# CONTROL.net
KiCad netlist of a schematic drawn in Altium Designer
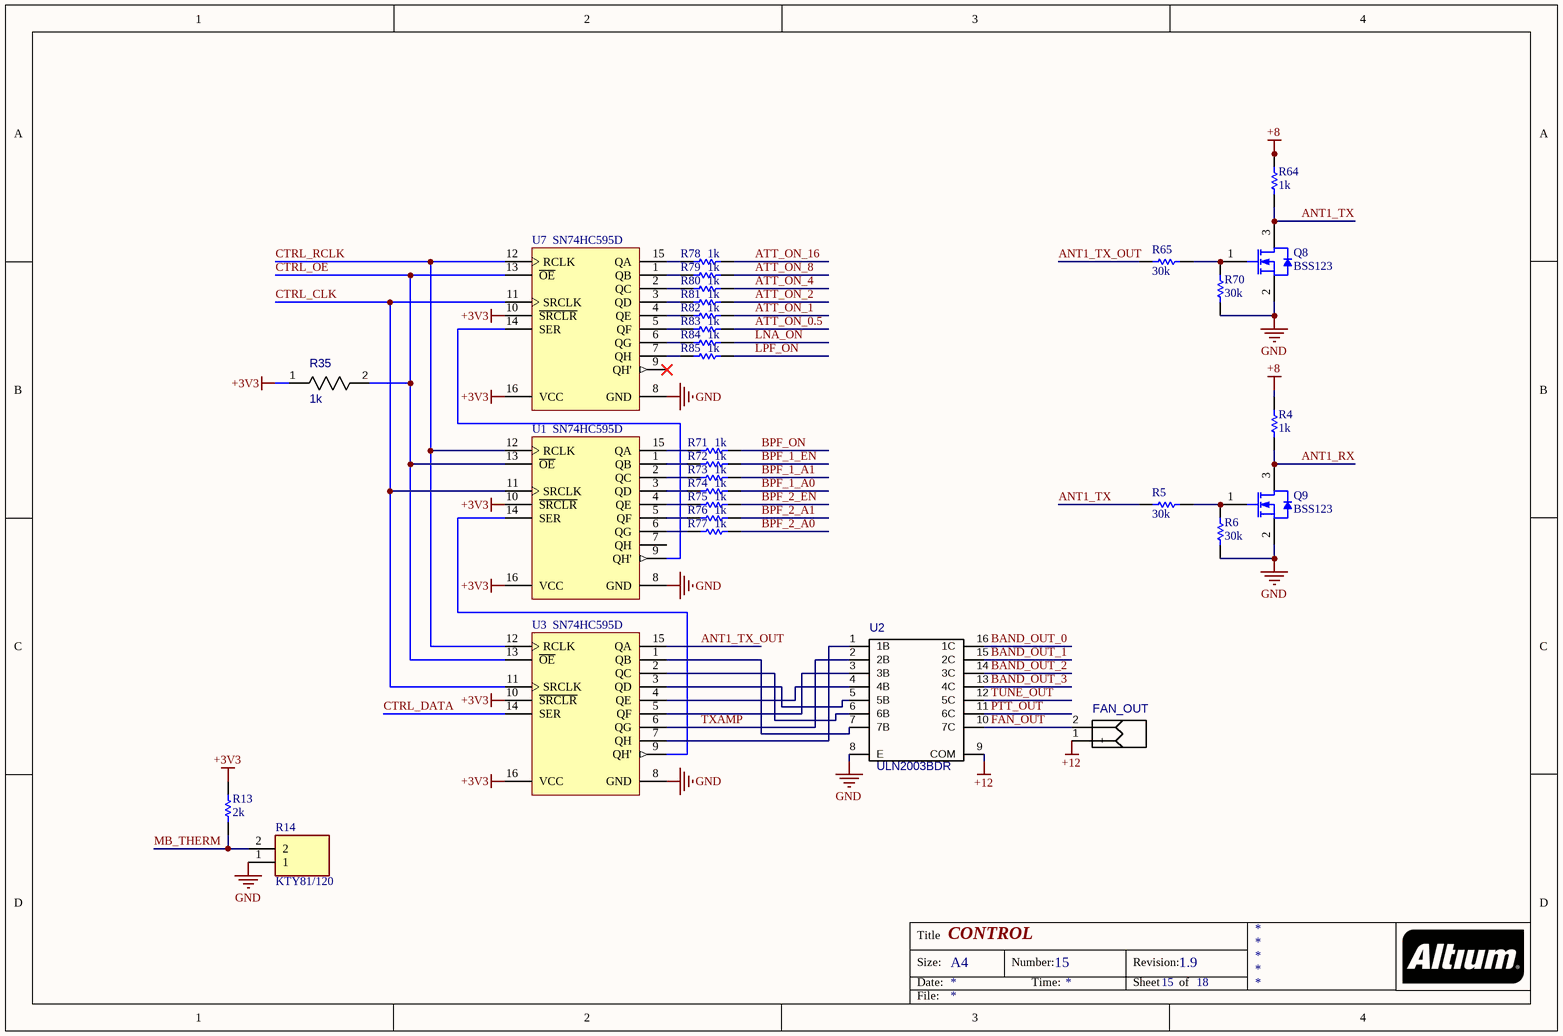
[diagram p0: CONTROL.SchDoc]

(export (version "E")
  (design (tool "Eeschema 10.0.6"))
  (components
    (comp (ref "FAN_OUT")
      (value "51022-0200")
      (footprint "51022-0200")
      (libsource (lib "*") (part "51022-0200"))
    )
    (comp (ref "Q8")
      (value "BSS123")
      (footprint "FAIR-SOT23-3_V")
      (fields (field (name "MANUFACTURER") "Fairchild"))
      (libsource (lib "Altium Content Vault") (part "NEMOS-GSD-3"))
    )
    (comp (ref "Q9")
      (value "BSS123")
      (footprint "FAIR-SOT23-3_V")
      (fields (field (name "MANUFACTURER") "Fairchild"))
      (libsource (lib "Altium Content Vault") (part "NEMOS-GSD-3"))
    )
    (comp (ref "R4")
      (value "1k")
      (footprint "RESC2013X60X40NL20T25")
      (description "RES_0805")
      (fields (field (name "MANUFACTURER") "Panasonic") (field (name "PART NUMBER") "ERA-6AEB303V"))
      (libsource (lib "Altium Content Vault") (part "RES"))
    )
    (comp (ref "R5")
      (value "30k")
      (footprint "RESC2013X60X40NL20T25")
      (description "RES_0805")
      (fields (field (name "MANUFACTURER") "Panasonic") (field (name "PART NUMBER") "ERA-6AEB303V"))
      (libsource (lib "Altium Content Vault") (part "RES"))
    )
    (comp (ref "R6")
      (value "30k")
      (footprint "RESC2013X60X40NL20T25")
      (description "RES_0805")
      (fields (field (name "MANUFACTURER") "Panasonic") (field (name "PART NUMBER") "ERA-6AEB303V"))
      (libsource (lib "Altium Content Vault") (part "RES"))
    )
    (comp (ref "R13")
      (value "2k")
      (footprint "RESC2013X60X40NL20T25")
      (description "RES_0805")
      (fields (field (name "MANUFACTURER") "Panasonic") (field (name "PART NUMBER") "ERA-6AEB303V"))
      (libsource (lib "Altium Content Vault") (part "RES"))
    )
    (comp (ref "R14")
      (value "KTY81/120")
      (footprint "SamacSys:TO254P420X460X770-2P")
      (description "Integrated Circuit")
      (fields (field (name "MANUFACTURER_PART_NUMBER") "KTY81/110"))
      (libsource (lib "*") (part "KTY81_110"))
    )
    (comp (ref "R35")
      (value "1k")
      (footprint "RES_0805")
      (description "RES_0805")
      (libsource (lib "*") (part "RES_0805"))
    )
    (comp (ref "R64")
      (value "1k")
      (footprint "RESC2013X60X40NL20T25")
      (description "RES_0805")
      (fields (field (name "MANUFACTURER") "Panasonic") (field (name "PART NUMBER") "ERA-6AEB303V"))
      (libsource (lib "Altium Content Vault") (part "RES"))
    )
    (comp (ref "R65")
      (value "30k")
      (footprint "RESC2013X60X40NL20T25")
      (description "RES_0805")
      (fields (field (name "MANUFACTURER") "Panasonic") (field (name "PART NUMBER") "ERA-6AEB303V"))
      (libsource (lib "Altium Content Vault") (part "RES"))
    )
    (comp (ref "R70")
      (value "30k")
      (footprint "RESC2013X60X40NL20T25")
      (description "RES_0805")
      (fields (field (name "MANUFACTURER") "Panasonic") (field (name "PART NUMBER") "ERA-6AEB303V"))
      (libsource (lib "Altium Content Vault") (part "RES"))
    )
    (comp (ref "R71")
      (value "1k")
      (footprint "RESC2013X60X40NL20T25")
      (description "RES_0805")
      (fields (field (name "MANUFACTURER") "Panasonic") (field (name "PART NUMBER") "ERA-6AEB303V"))
      (libsource (lib "Altium Content Vault") (part "RES"))
    )
    (comp (ref "R72")
      (value "1k")
      (footprint "RESC2013X60X40NL20T25")
      (description "RES_0805")
      (fields (field (name "MANUFACTURER") "Panasonic") (field (name "PART NUMBER") "ERA-6AEB303V"))
      (libsource (lib "Altium Content Vault") (part "RES"))
    )
    (comp (ref "R73")
      (value "1k")
      (footprint "RESC2013X60X40NL20T25")
      (description "RES_0805")
      (fields (field (name "MANUFACTURER") "Panasonic") (field (name "PART NUMBER") "ERA-6AEB303V"))
      (libsource (lib "Altium Content Vault") (part "RES"))
    )
    (comp (ref "R74")
      (value "1k")
      (footprint "RESC2013X60X40NL20T25")
      (description "RES_0805")
      (fields (field (name "MANUFACTURER") "Panasonic") (field (name "PART NUMBER") "ERA-6AEB303V"))
      (libsource (lib "Altium Content Vault") (part "RES"))
    )
    (comp (ref "R75")
      (value "1k")
      (footprint "RESC2013X60X40NL20T25")
      (description "RES_0805")
      (fields (field (name "MANUFACTURER") "Panasonic") (field (name "PART NUMBER") "ERA-6AEB303V"))
      (libsource (lib "Altium Content Vault") (part "RES"))
    )
    (comp (ref "R76")
      (value "1k")
      (footprint "RESC2013X60X40NL20T25")
      (description "RES_0805")
      (fields (field (name "MANUFACTURER") "Panasonic") (field (name "PART NUMBER") "ERA-6AEB303V"))
      (libsource (lib "Altium Content Vault") (part "RES"))
    )
    (comp (ref "R77")
      (value "1k")
      (footprint "RESC2013X60X40NL20T25")
      (description "RES_0805")
      (fields (field (name "MANUFACTURER") "Panasonic") (field (name "PART NUMBER") "ERA-6AEB303V"))
      (libsource (lib "Altium Content Vault") (part "RES"))
    )
    (comp (ref "R78")
      (value "1k")
      (footprint "RESC2013X60X40NL20T25")
      (description "RES_0805")
      (fields (field (name "MANUFACTURER") "Panasonic") (field (name "PART NUMBER") "ERA-6AEB303V"))
      (libsource (lib "Altium Content Vault") (part "RES"))
    )
    (comp (ref "R79")
      (value "1k")
      (footprint "RESC2013X60X40NL20T25")
      (description "RES_0805")
      (fields (field (name "MANUFACTURER") "Panasonic") (field (name "PART NUMBER") "ERA-6AEB303V"))
      (libsource (lib "Altium Content Vault") (part "RES"))
    )
    (comp (ref "R80")
      (value "1k")
      (footprint "RESC2013X60X40NL20T25")
      (description "RES_0805")
      (fields (field (name "MANUFACTURER") "Panasonic") (field (name "PART NUMBER") "ERA-6AEB303V"))
      (libsource (lib "Altium Content Vault") (part "RES"))
    )
    (comp (ref "R81")
      (value "1k")
      (footprint "RESC2013X60X40NL20T25")
      (description "RES_0805")
      (fields (field (name "MANUFACTURER") "Panasonic") (field (name "PART NUMBER") "ERA-6AEB303V"))
      (libsource (lib "Altium Content Vault") (part "RES"))
    )
    (comp (ref "R82")
      (value "1k")
      (footprint "RESC2013X60X40NL20T25")
      (description "RES_0805")
      (fields (field (name "MANUFACTURER") "Panasonic") (field (name "PART NUMBER") "ERA-6AEB303V"))
      (libsource (lib "Altium Content Vault") (part "RES"))
    )
    (comp (ref "R83")
      (value "1k")
      (footprint "RESC2013X60X40NL20T25")
      (description "RES_0805")
      (fields (field (name "MANUFACTURER") "Panasonic") (field (name "PART NUMBER") "ERA-6AEB303V"))
      (libsource (lib "Altium Content Vault") (part "RES"))
    )
    (comp (ref "R84")
      (value "1k")
      (footprint "RESC2013X60X40NL20T25")
      (description "RES_0805")
      (fields (field (name "MANUFACTURER") "Panasonic") (field (name "PART NUMBER") "ERA-6AEB303V"))
      (libsource (lib "Altium Content Vault") (part "RES"))
    )
    (comp (ref "R85")
      (value "1k")
      (footprint "RESC2013X60X40NL20T25")
      (description "RES_0805")
      (fields (field (name "MANUFACTURER") "Panasonic") (field (name "PART NUMBER") "ERA-6AEB303V"))
      (libsource (lib "Altium Content Vault") (part "RES"))
    )
    (comp (ref "U1")
      (value "SN74HC595D")
      (footprint "D0016A_L")
      (description "8-Bit Shift Registers With 3-State Output Registers, D0016A, TUBE")
      (fields
        (field (name "GENERIC PART NUMBER") "SN74HC595")
        (field (name "MANUFACTURER") "Texas Instruments")
      )
      (libsource (lib "Altium Content Vault") (part "TI-SN74XHCT595X_SN74LV595A-16"))
    )
    (comp (ref "U2")
      (value "ULN2003BDR")
      (footprint "ULN2003BDR")
      (libsource (lib "RF-UNIT") (part "ULN2003BDR"))
    )
    (comp (ref "U3")
      (value "SN74HC595D")
      (footprint "D0016A_L")
      (description "8-Bit Shift Registers With 3-State Output Registers, D0016A, TUBE")
      (fields
        (field (name "GENERIC PART NUMBER") "SN74HC595")
        (field (name "MANUFACTURER") "Texas Instruments")
      )
      (libsource (lib "Altium Content Vault") (part "TI-SN74XHCT595X_SN74LV595A-16"))
    )
    (comp (ref "U7")
      (value "SN74HC595D")
      (footprint "D0016A_L")
      (description "8-Bit Shift Registers With 3-State Output Registers, D0016A, TUBE")
      (fields
        (field (name "GENERIC PART NUMBER") "SN74HC595")
        (field (name "MANUFACTURER") "Texas Instruments")
      )
      (libsource (lib "Altium Content Vault") (part "TI-SN74XHCT595X_SN74LV595A-16"))
    )
  )
  (nets
    (net (code "1") (name "+3V3") (class "Default")
      (node (ref "R13") (pin "1") (pinfunction "1_1") (pintype "passive"))
      (node (ref "R35") (pin "1") (pinfunction "1_1") (pintype "passive"))
      (node (ref "U1") (pin "10") (pinfunction "~{SRCLR}_10") (pintype "passive"))
      (node (ref "U1") (pin "16") (pinfunction "VCC_16") (pintype "power_in"))
      (node (ref "U3") (pin "10") (pinfunction "~{SRCLR}_10") (pintype "passive"))
      (node (ref "U3") (pin "16") (pinfunction "VCC_16") (pintype "power_in"))
      (node (ref "U7") (pin "10") (pinfunction "~{SRCLR}_10") (pintype "passive"))
      (node (ref "U7") (pin "16") (pinfunction "VCC_16") (pintype "power_in"))
    )
    (net (code "2") (name "+8") (class "Default")
      (node (ref "R4") (pin "1") (pinfunction "1_1") (pintype "passive"))
      (node (ref "R64") (pin "1") (pinfunction "1_1") (pintype "passive"))
    )
    (net (code "3") (name "+12") (class "Default")
      (node (ref "FAN_OUT") (pin "1") (pinfunction "+_1") (pintype "passive"))
      (node (ref "U2") (pin "9") (pinfunction "COM_9") (pintype "passive"))
    )
    (net (code "5") (name "/ANT1_RX") (class "Default")
      (node (ref "Q9") (pin "3") (pinfunction "D_3") (pintype "passive"))
      (node (ref "R4") (pin "2") (pinfunction "2_2") (pintype "passive"))
    )
    (net (code "6") (name "/ANT1_TX") (class "Default")
      (node (ref "Q8") (pin "3") (pinfunction "D_3") (pintype "passive"))
      (node (ref "R5") (pin "2") (pinfunction "2_2") (pintype "passive"))
      (node (ref "R64") (pin "2") (pinfunction "2_2") (pintype "passive"))
    )
    (net (code "7") (name "/ANT1_TX_OUT") (class "Default")
      (node (ref "R65") (pin "2") (pinfunction "2_2") (pintype "passive"))
      (node (ref "U3") (pin "15") (pinfunction "QA_15") (pintype "tri_state"))
    )
    (net (code "8") (name "/ATT_ON_0.5") (class "Default")
      (node (ref "R83") (pin "1") (pinfunction "1_1") (pintype "passive"))
    )
    (net (code "9") (name "/ATT_ON_1") (class "Default")
      (node (ref "R82") (pin "1") (pinfunction "1_1") (pintype "passive"))
    )
    (net (code "10") (name "/ATT_ON_2") (class "Default")
      (node (ref "R81") (pin "1") (pinfunction "1_1") (pintype "passive"))
    )
    (net (code "11") (name "/ATT_ON_4") (class "Default")
      (node (ref "R80") (pin "1") (pinfunction "1_1") (pintype "passive"))
    )
    (net (code "12") (name "/ATT_ON_8") (class "Default")
      (node (ref "R79") (pin "1") (pinfunction "1_1") (pintype "passive"))
    )
    (net (code "13") (name "/ATT_ON_16") (class "Default")
      (node (ref "R78") (pin "1") (pinfunction "1_1") (pintype "passive"))
    )
    (net (code "14") (name "/BAND_OUT_0") (class "Default")
      (node (ref "U2") (pin "16") (pinfunction "1C_16") (pintype "passive"))
    )
    (net (code "15") (name "/BAND_OUT_1") (class "Default")
      (node (ref "U2") (pin "15") (pinfunction "2C_15") (pintype "passive"))
    )
    (net (code "16") (name "/BAND_OUT_2") (class "Default")
      (node (ref "U2") (pin "14") (pinfunction "3C_14") (pintype "passive"))
    )
    (net (code "17") (name "/BAND_OUT_3") (class "Default")
      (node (ref "U2") (pin "13") (pinfunction "4C_13") (pintype "passive"))
    )
    (net (code "18") (name "/BPF_1_A0") (class "Default")
      (node (ref "R74") (pin "1") (pinfunction "1_1") (pintype "passive"))
    )
    (net (code "19") (name "/BPF_1_A1") (class "Default")
      (node (ref "R73") (pin "1") (pinfunction "1_1") (pintype "passive"))
    )
    (net (code "20") (name "/BPF_1_EN") (class "Default")
      (node (ref "R72") (pin "1") (pinfunction "1_1") (pintype "passive"))
    )
    (net (code "21") (name "/BPF_2_A0") (class "Default")
      (node (ref "R77") (pin "1") (pinfunction "1_1") (pintype "passive"))
    )
    (net (code "22") (name "/BPF_2_A1") (class "Default")
      (node (ref "R76") (pin "1") (pinfunction "1_1") (pintype "passive"))
    )
    (net (code "23") (name "/BPF_2_EN") (class "Default")
      (node (ref "R75") (pin "1") (pinfunction "1_1") (pintype "passive"))
    )
    (net (code "24") (name "/BPF_ON") (class "Default")
      (node (ref "R71") (pin "1") (pinfunction "1_1") (pintype "passive"))
    )
    (net (code "25") (name "/CTRL_CLK") (class "Default")
      (node (ref "U1") (pin "11") (pinfunction "SRCLK_11") (pintype "passive"))
      (node (ref "U3") (pin "11") (pinfunction "SRCLK_11") (pintype "passive"))
      (node (ref "U7") (pin "11") (pinfunction "SRCLK_11") (pintype "passive"))
    )
    (net (code "26") (name "/CTRL_DATA") (class "Default")
      (node (ref "U3") (pin "14") (pinfunction "SER_14") (pintype "passive"))
    )
    (net (code "27") (name "/CTRL_OE") (class "Default")
      (node (ref "R35") (pin "2") (pinfunction "2_2") (pintype "passive"))
      (node (ref "U1") (pin "13") (pinfunction "~{OE}_13") (pintype "passive"))
      (node (ref "U3") (pin "13") (pinfunction "~{OE}_13") (pintype "passive"))
      (node (ref "U7") (pin "13") (pinfunction "~{OE}_13") (pintype "passive"))
    )
    (net (code "28") (name "/CTRL_RCLK") (class "Default")
      (node (ref "U1") (pin "12") (pinfunction "RCLK_12") (pintype "passive"))
      (node (ref "U3") (pin "12") (pinfunction "RCLK_12") (pintype "passive"))
      (node (ref "U7") (pin "12") (pinfunction "RCLK_12") (pintype "passive"))
    )
    (net (code "29") (name "/FAN_OUT") (class "Default")
      (node (ref "FAN_OUT") (pin "2") (pinfunction "-_2") (pintype "passive"))
      (node (ref "U2") (pin "10") (pinfunction "7C_10") (pintype "passive"))
    )
    (net (code "30") (name "/LNA_ON") (class "Default")
      (node (ref "R84") (pin "1") (pinfunction "1_1") (pintype "passive"))
    )
    (net (code "31") (name "/LPF_ON") (class "Default")
      (node (ref "R85") (pin "1") (pinfunction "1_1") (pintype "passive"))
    )
    (net (code "32") (name "/MB_THERM") (class "Default")
      (node (ref "R13") (pin "2") (pinfunction "2_2") (pintype "passive"))
      (node (ref "R14") (pin "2") (pinfunction "2_2") (pintype "passive"))
    )
    (net (code "33") (name "/PTT_OUT") (class "Default")
      (node (ref "U2") (pin "11") (pinfunction "6C_11") (pintype "passive"))
    )
    (net (code "34") (name "/TUNE_OUT") (class "Default")
      (node (ref "U2") (pin "12") (pinfunction "5C_12") (pintype "passive"))
    )
    (net (code "35") (name "/TXAMP") (class "Default")
      (node (ref "U2") (pin "2") (pinfunction "2B_2") (pintype "passive"))
      (node (ref "U3") (pin "6") (pinfunction "QG_6") (pintype "tri_state"))
    )
    (net (code "36") (name "GND") (class "Default")
      (node (ref "Q8") (pin "2") (pinfunction "S_2") (pintype "passive"))
      (node (ref "Q9") (pin "2") (pinfunction "S_2") (pintype "passive"))
      (node (ref "R14") (pin "1") (pinfunction "1_1") (pintype "passive"))
      (node (ref "R6") (pin "1") (pinfunction "1_1") (pintype "passive"))
      (node (ref "R70") (pin "1") (pinfunction "1_1") (pintype "passive"))
      (node (ref "U1") (pin "8") (pinfunction "GND_8") (pintype "power_in"))
      (node (ref "U2") (pin "8") (pinfunction "E_8") (pintype "passive"))
      (node (ref "U3") (pin "8") (pinfunction "GND_8") (pintype "power_in"))
      (node (ref "U7") (pin "8") (pinfunction "GND_8") (pintype "power_in"))
    )
    (net (code "37") (name "Net-(Q8-G)") (class "Default")
      (node (ref "Q8") (pin "1") (pinfunction "G_1") (pintype "passive"))
      (node (ref "R65") (pin "1") (pinfunction "1_1") (pintype "passive"))
      (node (ref "R70") (pin "2") (pinfunction "2_2") (pintype "passive"))
    )
    (net (code "38") (name "Net-(Q9-G)") (class "Default")
      (node (ref "Q9") (pin "1") (pinfunction "G_1") (pintype "passive"))
      (node (ref "R5") (pin "1") (pinfunction "1_1") (pintype "passive"))
      (node (ref "R6") (pin "2") (pinfunction "2_2") (pintype "passive"))
    )
    (net (code "39") (name "Net-(U1-QA)") (class "Default")
      (node (ref "R71") (pin "2") (pinfunction "2_2") (pintype "passive"))
      (node (ref "U1") (pin "15") (pinfunction "QA_15") (pintype "tri_state"))
    )
    (net (code "40") (name "Net-(U1-QB)") (class "Default")
      (node (ref "R72") (pin "2") (pinfunction "2_2") (pintype "passive"))
      (node (ref "U1") (pin "1") (pinfunction "QB_1") (pintype "tri_state"))
    )
    (net (code "41") (name "Net-(U1-QC)") (class "Default")
      (node (ref "R73") (pin "2") (pinfunction "2_2") (pintype "passive"))
      (node (ref "U1") (pin "2") (pinfunction "QC_2") (pintype "tri_state"))
    )
    (net (code "42") (name "Net-(U1-QD)") (class "Default")
      (node (ref "R74") (pin "2") (pinfunction "2_2") (pintype "passive"))
      (node (ref "U1") (pin "3") (pinfunction "QD_3") (pintype "tri_state"))
    )
    (net (code "43") (name "Net-(U1-QE)") (class "Default")
      (node (ref "R75") (pin "2") (pinfunction "2_2") (pintype "passive"))
      (node (ref "U1") (pin "4") (pinfunction "QE_4") (pintype "tri_state"))
    )
    (net (code "44") (name "Net-(U1-QF)") (class "Default")
      (node (ref "R76") (pin "2") (pinfunction "2_2") (pintype "passive"))
      (node (ref "U1") (pin "5") (pinfunction "QF_5") (pintype "tri_state"))
    )
    (net (code "45") (name "Net-(U1-QG)") (class "Default")
      (node (ref "R77") (pin "2") (pinfunction "2_2") (pintype "passive"))
      (node (ref "U1") (pin "6") (pinfunction "QG_6") (pintype "tri_state"))
    )
    (net (code "46") (name "Net-(U1-QH')") (class "Default")
      (node (ref "U1") (pin "9") (pinfunction "QH'_9") (pintype "output"))
      (node (ref "U7") (pin "14") (pinfunction "SER_14") (pintype "passive"))
    )
    (net (code "47") (name "Net-(U1-SER)") (class "Default")
      (node (ref "U1") (pin "14") (pinfunction "SER_14") (pintype "passive"))
      (node (ref "U3") (pin "9") (pinfunction "QH'_9") (pintype "output"))
    )
    (net (code "48") (name "Net-(U2-1B)") (class "Default")
      (node (ref "U2") (pin "1") (pinfunction "1B_1") (pintype "passive"))
      (node (ref "U3") (pin "7") (pinfunction "QH_7") (pintype "tri_state"))
    )
    (net (code "49") (name "Net-(U2-3B)") (class "Default")
      (node (ref "U2") (pin "3") (pinfunction "3B_3") (pintype "passive"))
      (node (ref "U3") (pin "5") (pinfunction "QF_5") (pintype "tri_state"))
    )
    (net (code "50") (name "Net-(U2-4B)") (class "Default")
      (node (ref "U2") (pin "4") (pinfunction "4B_4") (pintype "passive"))
      (node (ref "U3") (pin "4") (pinfunction "QE_4") (pintype "tri_state"))
    )
    (net (code "51") (name "Net-(U2-5B)") (class "Default")
      (node (ref "U2") (pin "5") (pinfunction "5B_5") (pintype "passive"))
      (node (ref "U3") (pin "3") (pinfunction "QD_3") (pintype "tri_state"))
    )
    (net (code "52") (name "Net-(U2-6B)") (class "Default")
      (node (ref "U2") (pin "6") (pinfunction "6B_6") (pintype "passive"))
      (node (ref "U3") (pin "2") (pinfunction "QC_2") (pintype "tri_state"))
    )
    (net (code "53") (name "Net-(U2-7B)") (class "Default")
      (node (ref "U2") (pin "7") (pinfunction "7B_7") (pintype "passive"))
      (node (ref "U3") (pin "1") (pinfunction "QB_1") (pintype "tri_state"))
    )
    (net (code "54") (name "Net-(U7-QA)") (class "Default")
      (node (ref "R78") (pin "2") (pinfunction "2_2") (pintype "passive"))
      (node (ref "U7") (pin "15") (pinfunction "QA_15") (pintype "tri_state"))
    )
    (net (code "55") (name "Net-(U7-QB)") (class "Default")
      (node (ref "R79") (pin "2") (pinfunction "2_2") (pintype "passive"))
      (node (ref "U7") (pin "1") (pinfunction "QB_1") (pintype "tri_state"))
    )
    (net (code "56") (name "Net-(U7-QC)") (class "Default")
      (node (ref "R80") (pin "2") (pinfunction "2_2") (pintype "passive"))
      (node (ref "U7") (pin "2") (pinfunction "QC_2") (pintype "tri_state"))
    )
    (net (code "57") (name "Net-(U7-QD)") (class "Default")
      (node (ref "R81") (pin "2") (pinfunction "2_2") (pintype "passive"))
      (node (ref "U7") (pin "3") (pinfunction "QD_3") (pintype "tri_state"))
    )
    (net (code "58") (name "Net-(U7-QE)") (class "Default")
      (node (ref "R82") (pin "2") (pinfunction "2_2") (pintype "passive"))
      (node (ref "U7") (pin "4") (pinfunction "QE_4") (pintype "tri_state"))
    )
    (net (code "59") (name "Net-(U7-QF)") (class "Default")
      (node (ref "R83") (pin "2") (pinfunction "2_2") (pintype "passive"))
      (node (ref "U7") (pin "5") (pinfunction "QF_5") (pintype "tri_state"))
    )
    (net (code "60") (name "Net-(U7-QG)") (class "Default")
      (node (ref "R84") (pin "2") (pinfunction "2_2") (pintype "passive"))
      (node (ref "U7") (pin "6") (pinfunction "QG_6") (pintype "tri_state"))
    )
    (net (code "61") (name "Net-(U7-QH)") (class "Default")
      (node (ref "R85") (pin "2") (pinfunction "2_2") (pintype "passive"))
      (node (ref "U7") (pin "7") (pinfunction "QH_7") (pintype "tri_state"))
    )
    (net (code "62") (name "unconnected-(U1-QH-Pad7)") (class "Default")
      (node (ref "U1") (pin "7") (pinfunction "QH_7") (pintype "tri_state"))
    )
    (net (code "63") (name "unconnected-(U7-QH'-Pad9)") (class "Default")
      (node (ref "U7") (pin "9") (pinfunction "QH'_9") (pintype "output+no_connect"))
    )
  )
)
